# controller-main_3.net
KiCad netlist of a schematic drawn in EAGLE
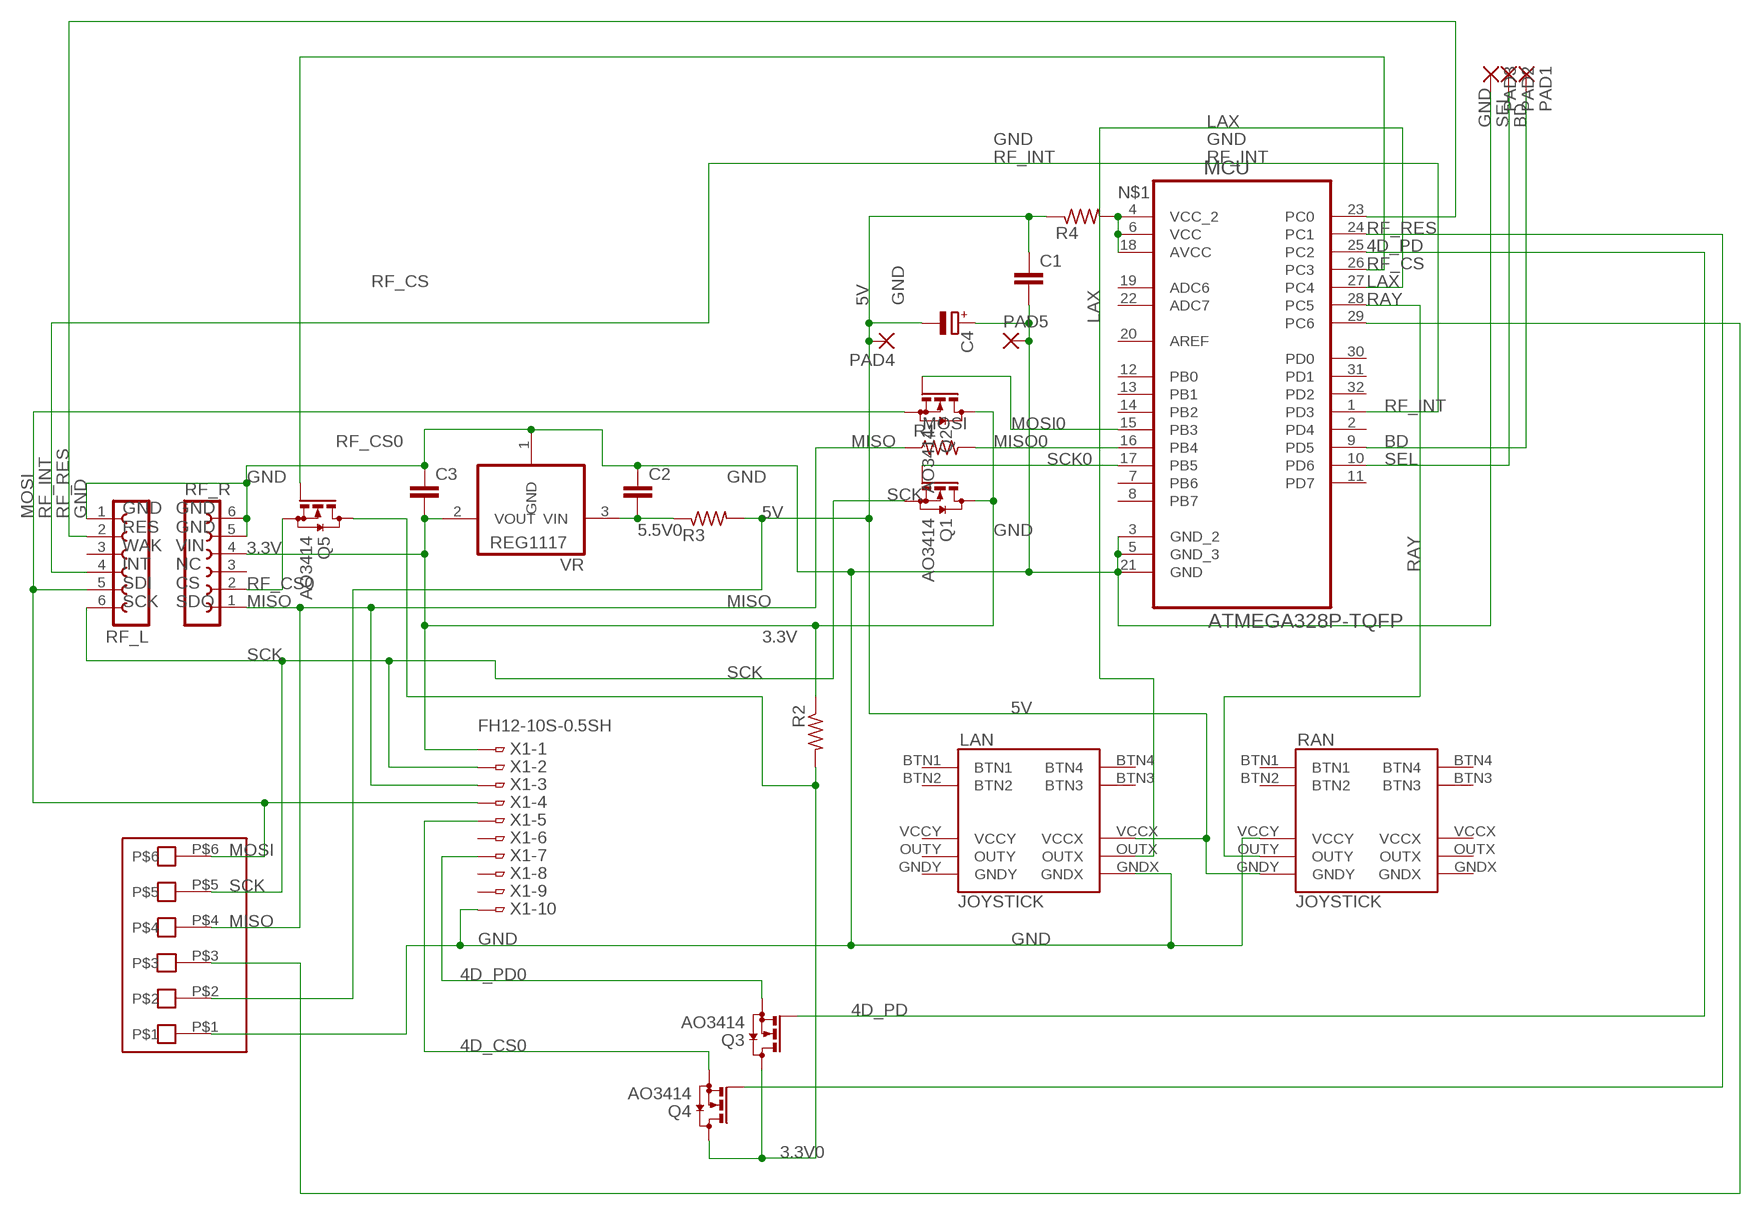
[diagram p0: schematic, sheet 1]

(export (version "E")
  (design (tool "Eeschema 10.0.6"))
  (components
    (comp (ref "C1")
      (value "C-EUC1206")
      (footprint "eagle-import:C1206")
      (libsource (lib "eagle-import") (part "C-EUC1206"))
    )
    (comp (ref "C2")
      (value "C-EUC1206")
      (footprint "eagle-import:C1206")
      (libsource (lib "eagle-import") (part "C-EUC1206"))
    )
    (comp (ref "C3")
      (value "C-EUC1206")
      (footprint "eagle-import:C1206")
      (libsource (lib "eagle-import") (part "C-EUC1206"))
    )
    (comp (ref "C4")
      (value "CPOL-EU153CLV-0505")
      (footprint "eagle-import:153CLV-0505")
      (libsource (lib "eagle-import") (part "CPOL-EU153CLV-0505"))
    )
    (comp (ref "LAN")
      (value "JOYSTICK")
      (footprint "eagle-import:JOYSTICK")
      (libsource (lib "eagle-import") (part "JOYSTICKJOYSTICKWBTN"))
    )
    (comp (ref "MCU")
      (value "ATMEGA328P-TQFP")
      (footprint "eagle-import:QFP80P900X900X120-32N")
      (fields (field (name "MPN") "ATMEGA328P-AU"))
      (libsource (lib "eagle-import") (part "ATMEGA328P-AU"))
    )
    (comp (ref "PAD1")
      (value "SMD2")
      (footprint "eagle-import:SMD1,27-2,54")
      (libsource (lib "eagle-import") (part "SMD2"))
    )
    (comp (ref "PAD2")
      (value "SMD2")
      (footprint "eagle-import:SMD1,27-2,54")
      (libsource (lib "eagle-import") (part "SMD2"))
    )
    (comp (ref "PAD3")
      (value "SMD2")
      (footprint "eagle-import:SMD1,27-2,54")
      (libsource (lib "eagle-import") (part "SMD2"))
    )
    (comp (ref "PAD4")
      (value "SMD5")
      (footprint "eagle-import:SMD2,54-5,08")
      (libsource (lib "eagle-import") (part "SMD5"))
    )
    (comp (ref "PAD5")
      (value "SMD5")
      (footprint "eagle-import:SMD2,54-5,08")
      (libsource (lib "eagle-import") (part "SMD5"))
    )
    (comp (ref "Q1")
      (value "AO3414")
      (footprint "eagle-import:SOT23")
      (libsource (lib "eagle-import") (part "BSS123"))
    )
    (comp (ref "Q2")
      (value "AO3414")
      (footprint "eagle-import:SOT23")
      (libsource (lib "eagle-import") (part "BSS123"))
    )
    (comp (ref "Q3")
      (value "AO3414")
      (footprint "eagle-import:SOT23")
      (libsource (lib "eagle-import") (part "BSS123"))
    )
    (comp (ref "Q4")
      (value "AO3414")
      (footprint "eagle-import:SOT23")
      (libsource (lib "eagle-import") (part "BSS123"))
    )
    (comp (ref "Q5")
      (value "AO3414")
      (footprint "eagle-import:SOT23")
      (libsource (lib "eagle-import") (part "BSS123"))
    )
    (comp (ref "R1")
      (value "R-US_R1206")
      (footprint "eagle-import:R1206")
      (libsource (lib "eagle-import") (part "R-US_R1206"))
    )
    (comp (ref "R2")
      (value "R-US_R1206")
      (footprint "eagle-import:R1206")
      (libsource (lib "eagle-import") (part "R-US_R1206"))
    )
    (comp (ref "R3")
      (value "R-US_R1206")
      (footprint "eagle-import:R1206")
      (libsource (lib "eagle-import") (part "R-US_R1206"))
    )
    (comp (ref "R4")
      (value "R-US_R1206")
      (footprint "eagle-import:R1206")
      (libsource (lib "eagle-import") (part "R-US_R1206"))
    )
    (comp (ref "RAN")
      (value "JOYSTICK")
      (footprint "eagle-import:JOYSTICK")
      (libsource (lib "eagle-import") (part "JOYSTICKJOYSTICKWBTN"))
    )
    (comp (ref "RF_L")
      (value "FE06-1")
      (footprint "eagle-import:FE06")
      (libsource (lib "eagle-import") (part "FE06-1"))
    )
    (comp (ref "RF_R")
      (value "FE06-1")
      (footprint "eagle-import:FE06")
      (libsource (lib "eagle-import") (part "FE06-1"))
    )
    (comp (ref "U$1")
      (value "JTECH-6PV")
      (footprint "eagle-import:PAK-6PV")
      (libsource (lib "eagle-import") (part "JTECH-6PV"))
    )
    (comp (ref "VR")
      (value "REG1117")
      (footprint "eagle-import:SOT223")
      (libsource (lib "eagle-import") (part "REG1117"))
    )
    (comp (ref "X1")
      (value "FH12-10S-0.5SH")
      (footprint "eagle-import:FH12-10S-0.5SH")
      (fields (field (name "MPN") "FH12-10S-0.5SH(55)"))
      (libsource (lib "eagle-import") (part "FH12-10S-0.5SH"))
    )
  )
  (nets
    (net (code "1") (name "/3.3V") (class "Default")
      (node (ref "C3") (pin "2") (pinfunction "2_2") (pintype "passive"))
      (node (ref "Q1") (pin "3") (pinfunction "D_3") (pintype "passive"))
      (node (ref "Q2") (pin "3") (pinfunction "D_3") (pintype "passive"))
      (node (ref "R2") (pin "1") (pinfunction "1_1") (pintype "passive"))
      (node (ref "RF_R") (pin "4") (pinfunction "4_4") (pintype "passive"))
      (node (ref "VR") (pin "2") (pinfunction "VOUT_2") (pintype "output"))
      (node (ref "X1") (pin "1") (pinfunction "1_1") (pintype "passive"))
    )
    (net (code "2") (name "/3.3V0") (class "Default")
      (node (ref "Q3") (pin "3") (pinfunction "D_3") (pintype "passive"))
      (node (ref "Q4") (pin "3") (pinfunction "D_3") (pintype "passive"))
      (node (ref "Q5") (pin "3") (pinfunction "D_3") (pintype "passive"))
      (node (ref "R2") (pin "2") (pinfunction "2_2") (pintype "passive"))
    )
    (net (code "3") (name "/4D_CS0") (class "Default")
      (node (ref "Q4") (pin "2") (pinfunction "S_2") (pintype "passive"))
      (node (ref "X1") (pin "5") (pinfunction "1_5") (pintype "passive"))
    )
    (net (code "4") (name "/4D_PD") (class "Default")
      (node (ref "MCU") (pin "25") (pinfunction "PC2_25") (pintype "bidirectional"))
      (node (ref "Q3") (pin "1") (pinfunction "G_1") (pintype "passive"))
    )
    (net (code "5") (name "/4D_PD0") (class "Default")
      (node (ref "Q3") (pin "2") (pinfunction "S_2") (pintype "passive"))
      (node (ref "X1") (pin "7") (pinfunction "1_7") (pintype "passive"))
    )
    (net (code "6") (name "/5.5V0") (class "Default")
      (node (ref "C2") (pin "2") (pinfunction "2_2") (pintype "passive"))
      (node (ref "R3") (pin "1") (pinfunction "1_1") (pintype "passive"))
      (node (ref "VR") (pin "3") (pinfunction "VIN_3") (pintype "input"))
    )
    (net (code "7") (name "/5V") (class "Default")
      (node (ref "C1") (pin "1") (pinfunction "1_1") (pintype "passive"))
      (node (ref "C4") (pin "-") (pinfunction "-_-") (pintype "passive"))
      (node (ref "LAN") (pin "VCCX") (pinfunction "VCCX_VCCX") (pintype "bidirectional"))
      (node (ref "PAD4") (pin "1") (pinfunction "P_1") (pintype "passive"))
      (node (ref "R3") (pin "2") (pinfunction "2_2") (pintype "passive"))
      (node (ref "R4") (pin "1") (pinfunction "1_1") (pintype "passive"))
      (node (ref "RAN") (pin "GNDY") (pinfunction "GNDY_GNDY") (pintype "bidirectional"))
      (node (ref "U$1") (pin "P$2") (pinfunction "P$2_P$2") (pintype "bidirectional"))
    )
    (net (code "8") (name "/BD") (class "Default")
      (node (ref "MCU") (pin "9") (pinfunction "PD5_9") (pintype "bidirectional"))
      (node (ref "PAD1") (pin "1") (pinfunction "P_1") (pintype "passive"))
    )
    (net (code "9") (name "/GND") (class "Default")
      (node (ref "C1") (pin "2") (pinfunction "2_2") (pintype "passive"))
      (node (ref "C2") (pin "1") (pinfunction "1_1") (pintype "passive"))
      (node (ref "C3") (pin "1") (pinfunction "1_1") (pintype "passive"))
      (node (ref "C4") (pin "+") (pinfunction "+_+") (pintype "passive"))
      (node (ref "LAN") (pin "GNDX") (pinfunction "GNDX_GNDX") (pintype "bidirectional"))
      (node (ref "MCU") (pin "21") (pinfunction "GND_21") (pintype "passive"))
      (node (ref "MCU") (pin "3") (pinfunction "GND_2_3") (pintype "passive"))
      (node (ref "MCU") (pin "5") (pinfunction "GND_3_5") (pintype "passive"))
      (node (ref "PAD3") (pin "1") (pinfunction "P_1") (pintype "passive"))
      (node (ref "PAD5") (pin "1") (pinfunction "P_1") (pintype "passive"))
      (node (ref "RAN") (pin "VCCY") (pinfunction "VCCY_VCCY") (pintype "bidirectional"))
      (node (ref "RF_L") (pin "1") (pinfunction "1_1") (pintype "passive"))
      (node (ref "RF_R") (pin "5") (pinfunction "5_5") (pintype "passive"))
      (node (ref "RF_R") (pin "6") (pinfunction "6_6") (pintype "passive"))
      (node (ref "U$1") (pin "P$1") (pinfunction "P$1_P$1") (pintype "bidirectional"))
      (node (ref "VR") (pin "1") (pinfunction "GND_1") (pintype "power_in"))
      (node (ref "X1") (pin "10") (pinfunction "1_10") (pintype "passive"))
    )
    (net (code "10") (name "/LAX") (class "Default")
      (node (ref "LAN") (pin "OUTX") (pinfunction "OUTX_OUTX") (pintype "bidirectional"))
      (node (ref "MCU") (pin "27") (pinfunction "PC4_27") (pintype "bidirectional"))
    )
    (net (code "11") (name "/MISO") (class "Default")
      (node (ref "R1") (pin "1") (pinfunction "1_1") (pintype "passive"))
      (node (ref "RF_R") (pin "1") (pinfunction "1_1") (pintype "passive"))
      (node (ref "U$1") (pin "P$4") (pinfunction "P$4_P$4") (pintype "bidirectional"))
      (node (ref "X1") (pin "3") (pinfunction "1_3") (pintype "passive"))
    )
    (net (code "12") (name "/MISO0") (class "Default")
      (node (ref "MCU") (pin "16") (pinfunction "PB4_16") (pintype "bidirectional"))
      (node (ref "R1") (pin "2") (pinfunction "2_2") (pintype "passive"))
    )
    (net (code "13") (name "/MOSI") (class "Default")
      (node (ref "Q2") (pin "2") (pinfunction "S_2") (pintype "passive"))
      (node (ref "RF_L") (pin "5") (pinfunction "5_5") (pintype "passive"))
      (node (ref "U$1") (pin "P$6") (pinfunction "P$6_P$6") (pintype "bidirectional"))
      (node (ref "X1") (pin "4") (pinfunction "1_4") (pintype "passive"))
    )
    (net (code "14") (name "/MOSI0") (class "Default")
      (node (ref "MCU") (pin "15") (pinfunction "PB3_15") (pintype "bidirectional"))
      (node (ref "Q2") (pin "1") (pinfunction "G_1") (pintype "passive"))
    )
    (net (code "15") (name "/N$1") (class "Default")
      (node (ref "MCU") (pin "18") (pinfunction "AVCC_18") (pintype "power_in"))
      (node (ref "MCU") (pin "4") (pinfunction "VCC_2_4") (pintype "power_in"))
      (node (ref "MCU") (pin "6") (pinfunction "VCC_6") (pintype "power_in"))
      (node (ref "R4") (pin "2") (pinfunction "2_2") (pintype "passive"))
    )
    (net (code "16") (name "/RAY") (class "Default")
      (node (ref "MCU") (pin "28") (pinfunction "PC5_28") (pintype "bidirectional"))
      (node (ref "RAN") (pin "OUTY") (pinfunction "OUTY_OUTY") (pintype "bidirectional"))
    )
    (net (code "17") (name "/RF_CS") (class "Default")
      (node (ref "MCU") (pin "26") (pinfunction "PC3_26") (pintype "bidirectional"))
      (node (ref "Q5") (pin "1") (pinfunction "G_1") (pintype "passive"))
    )
    (net (code "18") (name "/RF_CS0") (class "Default")
      (node (ref "Q5") (pin "2") (pinfunction "S_2") (pintype "passive"))
      (node (ref "RF_R") (pin "2") (pinfunction "2_2") (pintype "passive"))
    )
    (net (code "19") (name "/RF_INT") (class "Default")
      (node (ref "MCU") (pin "1") (pinfunction "PD3_1") (pintype "bidirectional"))
      (node (ref "RF_L") (pin "4") (pinfunction "4_4") (pintype "passive"))
    )
    (net (code "20") (name "/RF_RES") (class "Default")
      (node (ref "MCU") (pin "23") (pinfunction "PC0_23") (pintype "bidirectional"))
      (node (ref "RF_L") (pin "2") (pinfunction "2_2") (pintype "passive"))
    )
    (net (code "21") (name "/SCK") (class "Default")
      (node (ref "Q1") (pin "2") (pinfunction "S_2") (pintype "passive"))
      (node (ref "RF_L") (pin "6") (pinfunction "6_6") (pintype "passive"))
      (node (ref "U$1") (pin "P$5") (pinfunction "P$5_P$5") (pintype "bidirectional"))
      (node (ref "X1") (pin "2") (pinfunction "1_2") (pintype "passive"))
    )
    (net (code "22") (name "/SCK0") (class "Default")
      (node (ref "MCU") (pin "17") (pinfunction "PB5_17") (pintype "bidirectional"))
      (node (ref "Q1") (pin "1") (pinfunction "G_1") (pintype "passive"))
    )
    (net (code "23") (name "/SEL") (class "Default")
      (node (ref "MCU") (pin "10") (pinfunction "PD6_10") (pintype "bidirectional"))
      (node (ref "PAD2") (pin "1") (pinfunction "P_1") (pintype "passive"))
    )
    (net (code "24") (name "Net-(MCU-PC1)") (class "Default")
      (node (ref "MCU") (pin "24") (pinfunction "PC1_24") (pintype "bidirectional"))
      (node (ref "Q4") (pin "1") (pinfunction "G_1") (pintype "passive"))
    )
    (net (code "25") (name "Net-(MCU-PC6)") (class "Default")
      (node (ref "MCU") (pin "29") (pinfunction "PC6_29") (pintype "bidirectional"))
      (node (ref "U$1") (pin "P$3") (pinfunction "P$3_P$3") (pintype "bidirectional"))
    )
    (net (code "26") (name "unconnected-(LAN-PadBTN1)") (class "Default")
      (node (ref "LAN") (pin "BTN1") (pinfunction "BTN1_BTN1") (pintype "bidirectional"))
    )
    (net (code "27") (name "unconnected-(LAN-PadBTN2)") (class "Default")
      (node (ref "LAN") (pin "BTN2") (pinfunction "BTN2_BTN2") (pintype "bidirectional"))
    )
    (net (code "28") (name "unconnected-(LAN-PadBTN3)") (class "Default")
      (node (ref "LAN") (pin "BTN3") (pinfunction "BTN3_BTN3") (pintype "bidirectional"))
    )
    (net (code "29") (name "unconnected-(LAN-PadBTN4)") (class "Default")
      (node (ref "LAN") (pin "BTN4") (pinfunction "BTN4_BTN4") (pintype "bidirectional"))
    )
    (net (code "30") (name "unconnected-(LAN-PadGNDY)") (class "Default")
      (node (ref "LAN") (pin "GNDY") (pinfunction "GNDY_GNDY") (pintype "bidirectional"))
    )
    (net (code "31") (name "unconnected-(LAN-PadOUTY)") (class "Default")
      (node (ref "LAN") (pin "OUTY") (pinfunction "OUTY_OUTY") (pintype "bidirectional"))
    )
    (net (code "32") (name "unconnected-(LAN-PadVCCY)") (class "Default")
      (node (ref "LAN") (pin "VCCY") (pinfunction "VCCY_VCCY") (pintype "bidirectional"))
    )
    (net (code "33") (name "unconnected-(MCU-ADC6-Pad19)") (class "Default")
      (node (ref "MCU") (pin "19") (pinfunction "ADC6_19") (pintype "input"))
    )
    (net (code "34") (name "unconnected-(MCU-ADC7-Pad22)") (class "Default")
      (node (ref "MCU") (pin "22") (pinfunction "ADC7_22") (pintype "input"))
    )
    (net (code "35") (name "unconnected-(MCU-AREF-Pad20)") (class "Default")
      (node (ref "MCU") (pin "20") (pinfunction "AREF_20") (pintype "input"))
    )
    (net (code "36") (name "unconnected-(MCU-PB0-Pad12)") (class "Default")
      (node (ref "MCU") (pin "12") (pinfunction "PB0_12") (pintype "bidirectional"))
    )
    (net (code "37") (name "unconnected-(MCU-PB1-Pad13)") (class "Default")
      (node (ref "MCU") (pin "13") (pinfunction "PB1_13") (pintype "bidirectional"))
    )
    (net (code "38") (name "unconnected-(MCU-PB2-Pad14)") (class "Default")
      (node (ref "MCU") (pin "14") (pinfunction "PB2_14") (pintype "bidirectional"))
    )
    (net (code "39") (name "unconnected-(MCU-PB6-Pad7)") (class "Default")
      (node (ref "MCU") (pin "7") (pinfunction "PB6_7") (pintype "bidirectional"))
    )
    (net (code "40") (name "unconnected-(MCU-PB7-Pad8)") (class "Default")
      (node (ref "MCU") (pin "8") (pinfunction "PB7_8") (pintype "bidirectional"))
    )
    (net (code "41") (name "unconnected-(MCU-PD0-Pad30)") (class "Default")
      (node (ref "MCU") (pin "30") (pinfunction "PD0_30") (pintype "bidirectional"))
    )
    (net (code "42") (name "unconnected-(MCU-PD1-Pad31)") (class "Default")
      (node (ref "MCU") (pin "31") (pinfunction "PD1_31") (pintype "bidirectional"))
    )
    (net (code "43") (name "unconnected-(MCU-PD2-Pad32)") (class "Default")
      (node (ref "MCU") (pin "32") (pinfunction "PD2_32") (pintype "bidirectional"))
    )
    (net (code "44") (name "unconnected-(MCU-PD4-Pad2)") (class "Default")
      (node (ref "MCU") (pin "2") (pinfunction "PD4_2") (pintype "bidirectional"))
    )
    (net (code "45") (name "unconnected-(MCU-PD7-Pad11)") (class "Default")
      (node (ref "MCU") (pin "11") (pinfunction "PD7_11") (pintype "bidirectional"))
    )
    (net (code "46") (name "unconnected-(RAN-PadBTN1)") (class "Default")
      (node (ref "RAN") (pin "BTN1") (pinfunction "BTN1_BTN1") (pintype "bidirectional"))
    )
    (net (code "47") (name "unconnected-(RAN-PadBTN2)") (class "Default")
      (node (ref "RAN") (pin "BTN2") (pinfunction "BTN2_BTN2") (pintype "bidirectional"))
    )
    (net (code "48") (name "unconnected-(RAN-PadBTN3)") (class "Default")
      (node (ref "RAN") (pin "BTN3") (pinfunction "BTN3_BTN3") (pintype "bidirectional"))
    )
    (net (code "49") (name "unconnected-(RAN-PadBTN4)") (class "Default")
      (node (ref "RAN") (pin "BTN4") (pinfunction "BTN4_BTN4") (pintype "bidirectional"))
    )
    (net (code "50") (name "unconnected-(RAN-PadGNDX)") (class "Default")
      (node (ref "RAN") (pin "GNDX") (pinfunction "GNDX_GNDX") (pintype "bidirectional"))
    )
    (net (code "51") (name "unconnected-(RAN-PadOUTX)") (class "Default")
      (node (ref "RAN") (pin "OUTX") (pinfunction "OUTX_OUTX") (pintype "bidirectional"))
    )
    (net (code "52") (name "unconnected-(RAN-PadVCCX)") (class "Default")
      (node (ref "RAN") (pin "VCCX") (pinfunction "VCCX_VCCX") (pintype "bidirectional"))
    )
    (net (code "53") (name "unconnected-(RF_L-Pad3)") (class "Default")
      (node (ref "RF_L") (pin "3") (pinfunction "3_3") (pintype "passive"))
    )
    (net (code "54") (name "unconnected-(RF_R-Pad3)") (class "Default")
      (node (ref "RF_R") (pin "3") (pinfunction "3_3") (pintype "passive"))
    )
    (net (code "55") (name "unconnected-(X1G-1-Pad6)") (class "Default")
      (node (ref "X1") (pin "6") (pinfunction "1_6") (pintype "passive"))
    )
    (net (code "56") (name "unconnected-(X1I-1-Pad8)") (class "Default")
      (node (ref "X1") (pin "8") (pinfunction "1_8") (pintype "passive"))
    )
    (net (code "57") (name "unconnected-(X1J-1-Pad9)") (class "Default")
      (node (ref "X1") (pin "9") (pinfunction "1_9") (pintype "passive"))
    )
  )
)
